# SOT23-6.net
KiCad netlist of a schematic drawn in EAGLE
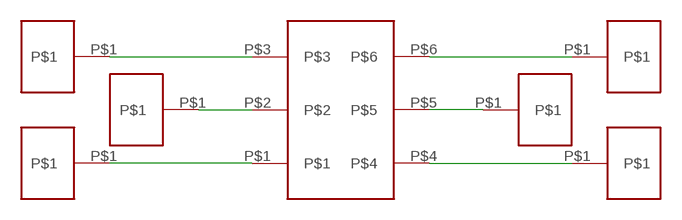
[diagram p0: schematic, sheet 1]

(export (version "E")
  (design (tool "Eeschema 10.0.6"))
  (components
    (comp (ref "U$1")
      (value "SOT23-6")
      (footprint "eagle-import:SOT23-6")
      (libsource (lib "eagle-import") (part "SOT23-6"))
    )
    (comp (ref "U$2")
      (value "PAD50X100MIL")
      (footprint "eagle-import:100X50MIL_PAD")
      (libsource (lib "eagle-import") (part "PAD50X100MIL"))
    )
    (comp (ref "U$3")
      (value "PAD50X100MIL")
      (footprint "eagle-import:100X50MIL_PAD")
      (libsource (lib "eagle-import") (part "PAD50X100MIL"))
    )
    (comp (ref "U$4")
      (value "PAD50X100MIL")
      (footprint "eagle-import:100X50MIL_PAD")
      (libsource (lib "eagle-import") (part "PAD50X100MIL"))
    )
    (comp (ref "U$5")
      (value "PAD50X100MIL")
      (footprint "eagle-import:100X50MIL_PAD")
      (libsource (lib "eagle-import") (part "PAD50X100MIL"))
    )
    (comp (ref "U$6")
      (value "PAD50X100MIL")
      (footprint "eagle-import:100X50MIL_PAD")
      (libsource (lib "eagle-import") (part "PAD50X100MIL"))
    )
    (comp (ref "U$7")
      (value "PAD50X100MIL")
      (footprint "eagle-import:100X50MIL_PAD")
      (libsource (lib "eagle-import") (part "PAD50X100MIL"))
    )
  )
  (nets
    (net (code "1") (name "Net-(U$1-PadP$1)") (class "Default")
      (node (ref "U$1") (pin "P$1") (pinfunction "P$1_P$1") (pintype "bidirectional"))
      (node (ref "U$4") (pin "P$1") (pinfunction "P$1_P$1") (pintype "bidirectional"))
    )
    (net (code "2") (name "Net-(U$1-PadP$2)") (class "Default")
      (node (ref "U$1") (pin "P$2") (pinfunction "P$2_P$2") (pintype "bidirectional"))
      (node (ref "U$2") (pin "P$1") (pinfunction "P$1_P$1") (pintype "bidirectional"))
    )
    (net (code "3") (name "Net-(U$1-PadP$3)") (class "Default")
      (node (ref "U$1") (pin "P$3") (pinfunction "P$3_P$3") (pintype "bidirectional"))
      (node (ref "U$3") (pin "P$1") (pinfunction "P$1_P$1") (pintype "bidirectional"))
    )
    (net (code "4") (name "Net-(U$1-PadP$4)") (class "Default")
      (node (ref "U$1") (pin "P$4") (pinfunction "P$4_P$4") (pintype "bidirectional"))
      (node (ref "U$7") (pin "P$1") (pinfunction "P$1_P$1") (pintype "bidirectional"))
    )
    (net (code "5") (name "Net-(U$1-PadP$5)") (class "Default")
      (node (ref "U$1") (pin "P$5") (pinfunction "P$5_P$5") (pintype "bidirectional"))
      (node (ref "U$5") (pin "P$1") (pinfunction "P$1_P$1") (pintype "bidirectional"))
    )
    (net (code "6") (name "Net-(U$1-PadP$6)") (class "Default")
      (node (ref "U$1") (pin "P$6") (pinfunction "P$6_P$6") (pintype "bidirectional"))
      (node (ref "U$6") (pin "P$1") (pinfunction "P$1_P$1") (pintype "bidirectional"))
    )
  )
)
